# SAM_15x15_v4.net
KiCad netlist of a schematic drawn in EAGLE
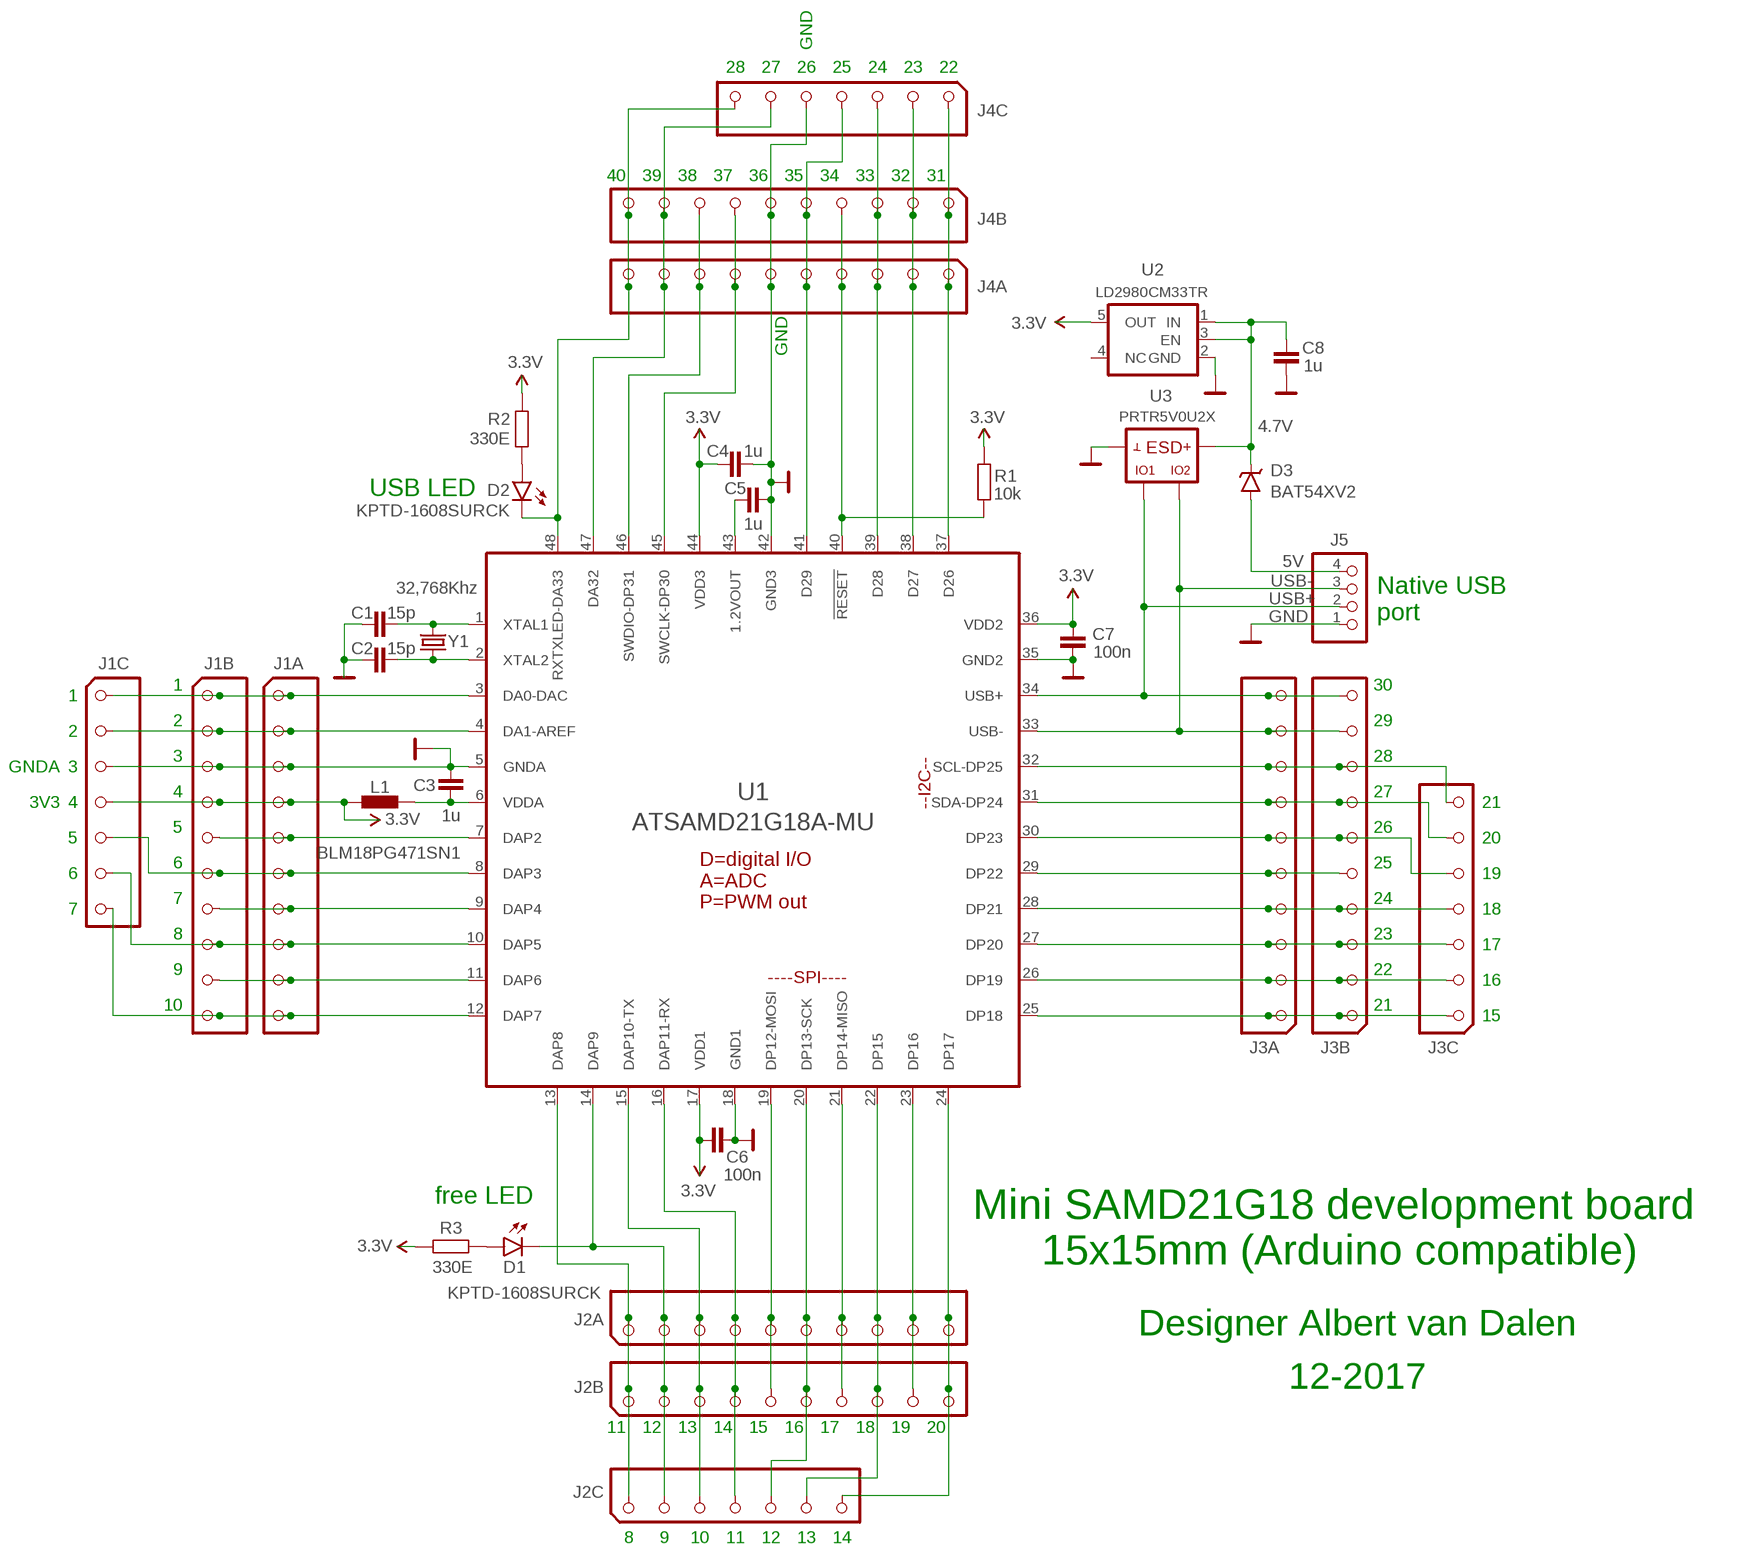
[diagram p0: schematic, sheet 1]

(export (version "E")
  (design (tool "Eeschema 10.0.6"))
  (components
    (comp (ref "C1")
      (value "15p")
      (footprint "eagle-import:0402-SMALL")
      (libsource (lib "eagle-import") (part "SMD-C-0402-SMALL"))
    )
    (comp (ref "C2")
      (value "15p")
      (footprint "eagle-import:0402-SMALL")
      (libsource (lib "eagle-import") (part "SMD-C-0402-SMALL"))
    )
    (comp (ref "C3")
      (value "1u")
      (footprint "eagle-import:0402-SMALL")
      (libsource (lib "eagle-import") (part "SMD-C-0402-SMALL"))
    )
    (comp (ref "C4")
      (value "1u")
      (footprint "eagle-import:0402-SMALL")
      (libsource (lib "eagle-import") (part "SMD-C-0402-SMALL"))
    )
    (comp (ref "C5")
      (value "1u")
      (footprint "eagle-import:0402-SMALL")
      (libsource (lib "eagle-import") (part "SMD-C-0402-SMALL"))
    )
    (comp (ref "C6")
      (value "100n")
      (footprint "eagle-import:0402-SMALL")
      (libsource (lib "eagle-import") (part "SMD-C-0402-SMALL"))
    )
    (comp (ref "C7")
      (value "100n")
      (footprint "eagle-import:0402-SMALL")
      (libsource (lib "eagle-import") (part "SMD-C-0402-SMALL"))
    )
    (comp (ref "C8")
      (value "1u")
      (footprint "eagle-import:0402-SMALL")
      (libsource (lib "eagle-import") (part "SMD-C-0402-SMALL"))
    )
    (comp (ref "D1")
      (value "KPTD-1608SURCK")
      (footprint "eagle-import:LED-0603")
      (libsource (lib "eagle-import") (part "LED"))
    )
    (comp (ref "D2")
      (value "KPTD-1608SURCK")
      (footprint "eagle-import:LED-0603")
      (libsource (lib "eagle-import") (part "LED"))
    )
    (comp (ref "D3")
      (value "BAT54XV2")
      (footprint "eagle-import:SOD523")
      (libsource (lib "eagle-import") (part "DIODE-SMDSOD523"))
    )
    (comp (ref "J1A")
      (value "JST-10SAM50")
      (footprint "eagle-import:1.27MM-10P-SAM50")
      (libsource (lib "eagle-import") (part "JST-10SAM50"))
    )
    (comp (ref "J1B")
      (value "JST-101X10")
      (footprint "eagle-import:1X10")
      (libsource (lib "eagle-import") (part "JST-101X10"))
    )
    (comp (ref "J1C")
      (value "SAM7SAM7")
      (footprint "eagle-import:SAM7")
      (libsource (lib "eagle-import") (part "SAM7SAM7"))
    )
    (comp (ref "J2A")
      (value "JST-10SAM50")
      (footprint "eagle-import:1.27MM-10P-SAM50")
      (libsource (lib "eagle-import") (part "JST-10SAM50"))
    )
    (comp (ref "J2B")
      (value "JST-101X10")
      (footprint "eagle-import:1X10")
      (libsource (lib "eagle-import") (part "JST-101X10"))
    )
    (comp (ref "J2C")
      (value "SAM7SAM7")
      (footprint "eagle-import:SAM7")
      (libsource (lib "eagle-import") (part "SAM7SAM7"))
    )
    (comp (ref "J3A")
      (value "JST-10SAM50")
      (footprint "eagle-import:1.27MM-10P-SAM50")
      (libsource (lib "eagle-import") (part "JST-10SAM50"))
    )
    (comp (ref "J3B")
      (value "JST-101X10")
      (footprint "eagle-import:1X10")
      (libsource (lib "eagle-import") (part "JST-101X10"))
    )
    (comp (ref "J3C")
      (value "SAM7SAM7")
      (footprint "eagle-import:SAM7")
      (libsource (lib "eagle-import") (part "SAM7SAM7"))
    )
    (comp (ref "J4A")
      (value "JST-10SAM50")
      (footprint "eagle-import:1.27MM-10P-SAM50")
      (libsource (lib "eagle-import") (part "JST-10SAM50"))
    )
    (comp (ref "J4B")
      (value "JST-101X10")
      (footprint "eagle-import:1X10")
      (libsource (lib "eagle-import") (part "JST-101X10"))
    )
    (comp (ref "J4C")
      (value "SAM7SAM7")
      (footprint "eagle-import:SAM7")
      (libsource (lib "eagle-import") (part "SAM7SAM7"))
    )
    (comp (ref "J5")
      (value "Header 4p")
      (footprint "eagle-import:1X04")
      (libsource (lib "eagle-import") (part "JST-41X04"))
    )
    (comp (ref "L1")
      (value "BLM18PG471SN1")
      (footprint "eagle-import:ARDUINO_C0603")
      (libsource (lib "eagle-import") (part "ARDUINO_INDUCTOR-0603"))
    )
    (comp (ref "R1")
      (value "10k")
      (footprint "eagle-import:0402-SMALL")
      (libsource (lib "eagle-import") (part "SMD-R-0402-SMALL"))
    )
    (comp (ref "R2")
      (value "330E")
      (footprint "eagle-import:0402-SMALL")
      (libsource (lib "eagle-import") (part "SMD-R-0402-SMALL"))
    )
    (comp (ref "R3")
      (value "330E")
      (footprint "eagle-import:0402-SMALL")
      (libsource (lib "eagle-import") (part "SMD-R-0402-SMALL"))
    )
    (comp (ref "U1")
      (value "ATSAMD21G18A-MU")
      (footprint "eagle-import:QFN-48")
      (libsource (lib "eagle-import") (part "ATSAMD21G-M"))
    )
    (comp (ref "U2")
      (value "LD2980CM33TR")
      (footprint "eagle-import:SOT23-5")
      (libsource (lib "eagle-import") (part "AP2112K-3.3TRG1"))
    )
    (comp (ref "U3")
      (value "PRTR5V0U2X")
      (footprint "eagle-import:SOT143B")
      (libsource (lib "eagle-import") (part "PRTR5V0U2X"))
    )
    (comp (ref "Y1")
      (value "32,768Khz")
      (footprint "eagle-import:CRYSTAL-SMD-3.2X1.5MM")
      (libsource (lib "eagle-import") (part "CRYSTAL-SMD"))
    )
  )
  (nets
    (net (code "1") (name "/3.3V") (class "Default")
      (node (ref "C4") (pin "2") (pinfunction "2_2") (pintype "passive"))
      (node (ref "C6") (pin "2") (pinfunction "2_2") (pintype "passive"))
      (node (ref "C7") (pin "2") (pinfunction "2_2") (pintype "passive"))
      (node (ref "J1A") (pin "4") (pinfunction "4_4") (pintype "passive"))
      (node (ref "J1B") (pin "4") (pinfunction "4_4") (pintype "passive"))
      (node (ref "J1C") (pin "4") (pinfunction "4_4") (pintype "passive"))
      (node (ref "L1") (pin "1") (pinfunction "1_1") (pintype "passive"))
      (node (ref "R1") (pin "2") (pinfunction "2_2") (pintype "passive"))
      (node (ref "R2") (pin "2") (pinfunction "2_2") (pintype "passive"))
      (node (ref "R3") (pin "2") (pinfunction "2_2") (pintype "passive"))
      (node (ref "U1") (pin "17") (pinfunction "VDD1_17") (pintype "bidirectional"))
      (node (ref "U1") (pin "36") (pinfunction "VDD2_36") (pintype "bidirectional"))
      (node (ref "U1") (pin "44") (pinfunction "VDD3_44") (pintype "bidirectional"))
      (node (ref "U2") (pin "5") (pinfunction "OUT_5") (pintype "passive"))
    )
    (net (code "2") (name "/4.7V") (class "Default")
      (node (ref "C8") (pin "2") (pinfunction "2_2") (pintype "passive"))
      (node (ref "D3") (pin "C") (pinfunction "C_C") (pintype "passive"))
      (node (ref "U2") (pin "1") (pinfunction "IN_1") (pintype "input"))
      (node (ref "U2") (pin "3") (pinfunction "EN_3") (pintype "input"))
      (node (ref "U3") (pin "4") (pinfunction "VCC_4") (pintype "bidirectional"))
    )
    (net (code "3") (name "/5V") (class "Default")
      (node (ref "D3") (pin "A") (pinfunction "A_A") (pintype "passive"))
      (node (ref "J5") (pin "4") (pinfunction "4_4") (pintype "passive"))
    )
    (net (code "4") (name "/USB+") (class "Default")
      (node (ref "J3A") (pin "10") (pinfunction "10_10") (pintype "passive"))
      (node (ref "J3B") (pin "10") (pinfunction "10_10") (pintype "passive"))
      (node (ref "J5") (pin "2") (pinfunction "2_2") (pintype "passive"))
      (node (ref "U1") (pin "34") (pinfunction "USB+_34") (pintype "bidirectional"))
      (node (ref "U3") (pin "3") (pinfunction "IO1_3") (pintype "bidirectional"))
    )
    (net (code "5") (name "/USB-") (class "Default")
      (node (ref "J3A") (pin "9") (pinfunction "9_9") (pintype "passive"))
      (node (ref "J3B") (pin "9") (pinfunction "9_9") (pintype "passive"))
      (node (ref "J5") (pin "3") (pinfunction "3_3") (pintype "passive"))
      (node (ref "U1") (pin "33") (pinfunction "USB-_33") (pintype "bidirectional"))
      (node (ref "U3") (pin "2") (pinfunction "IO2_2") (pintype "bidirectional"))
    )
    (net (code "6") (name "GND") (class "Default")
      (node (ref "C1") (pin "2") (pinfunction "2_2") (pintype "passive"))
      (node (ref "C2") (pin "2") (pinfunction "2_2") (pintype "passive"))
      (node (ref "C3") (pin "2") (pinfunction "2_2") (pintype "passive"))
      (node (ref "C4") (pin "1") (pinfunction "1_1") (pintype "passive"))
      (node (ref "C5") (pin "1") (pinfunction "1_1") (pintype "passive"))
      (node (ref "C6") (pin "1") (pinfunction "1_1") (pintype "passive"))
      (node (ref "C7") (pin "1") (pinfunction "1_1") (pintype "passive"))
      (node (ref "C8") (pin "1") (pinfunction "1_1") (pintype "passive"))
      (node (ref "J1A") (pin "3") (pinfunction "3_3") (pintype "passive"))
      (node (ref "J1B") (pin "3") (pinfunction "3_3") (pintype "passive"))
      (node (ref "J1C") (pin "3") (pinfunction "3_3") (pintype "passive"))
      (node (ref "J4A") (pin "6") (pinfunction "6_6") (pintype "passive"))
      (node (ref "J4B") (pin "6") (pinfunction "6_6") (pintype "passive"))
      (node (ref "J4C") (pin "5") (pinfunction "5_5") (pintype "passive"))
      (node (ref "J5") (pin "1") (pinfunction "1_1") (pintype "passive"))
      (node (ref "U1") (pin "18") (pinfunction "GND1_18") (pintype "bidirectional"))
      (node (ref "U1") (pin "35") (pinfunction "GND2_35") (pintype "bidirectional"))
      (node (ref "U1") (pin "42") (pinfunction "GND3_42") (pintype "bidirectional"))
      (node (ref "U1") (pin "5") (pinfunction "GNDA_5") (pintype "bidirectional"))
      (node (ref "U2") (pin "2") (pinfunction "GND_2") (pintype "input"))
      (node (ref "U3") (pin "1") (pinfunction "GND_1") (pintype "bidirectional"))
    )
    (net (code "7") (name "Net-(D1-PadA)") (class "Default")
      (node (ref "D1") (pin "A") (pinfunction "A_A") (pintype "passive"))
      (node (ref "R3") (pin "1") (pinfunction "1_1") (pintype "passive"))
    )
    (net (code "8") (name "Net-(D2-PadA)") (class "Default")
      (node (ref "D2") (pin "A") (pinfunction "A_A") (pintype "passive"))
      (node (ref "R2") (pin "1") (pinfunction "1_1") (pintype "passive"))
    )
    (net (code "9") (name "Net-(U1-1.2VOUT)") (class "Default")
      (node (ref "C5") (pin "2") (pinfunction "2_2") (pintype "passive"))
      (node (ref "U1") (pin "43") (pinfunction "1.2VOUT_43") (pintype "bidirectional"))
    )
    (net (code "10") (name "Net-(U1-D26)") (class "Default")
      (node (ref "J4A") (pin "1") (pinfunction "1_1") (pintype "passive"))
      (node (ref "J4B") (pin "1") (pinfunction "1_1") (pintype "passive"))
      (node (ref "J4C") (pin "1") (pinfunction "1_1") (pintype "passive"))
      (node (ref "U1") (pin "37") (pinfunction "D26_37") (pintype "bidirectional"))
    )
    (net (code "11") (name "Net-(U1-D27)") (class "Default")
      (node (ref "J4A") (pin "2") (pinfunction "2_2") (pintype "passive"))
      (node (ref "J4B") (pin "2") (pinfunction "2_2") (pintype "passive"))
      (node (ref "J4C") (pin "2") (pinfunction "2_2") (pintype "passive"))
      (node (ref "U1") (pin "38") (pinfunction "D27_38") (pintype "bidirectional"))
    )
    (net (code "12") (name "Net-(U1-D28)") (class "Default")
      (node (ref "J4A") (pin "3") (pinfunction "3_3") (pintype "passive"))
      (node (ref "J4B") (pin "3") (pinfunction "3_3") (pintype "passive"))
      (node (ref "J4C") (pin "3") (pinfunction "3_3") (pintype "passive"))
      (node (ref "U1") (pin "39") (pinfunction "D28_39") (pintype "bidirectional"))
    )
    (net (code "13") (name "Net-(U1-D29)") (class "Default")
      (node (ref "J4A") (pin "5") (pinfunction "5_5") (pintype "passive"))
      (node (ref "J4B") (pin "5") (pinfunction "5_5") (pintype "passive"))
      (node (ref "J4C") (pin "4") (pinfunction "4_4") (pintype "passive"))
      (node (ref "U1") (pin "41") (pinfunction "D29_41") (pintype "bidirectional"))
    )
    (net (code "14") (name "Net-(U1-DA0-DAC)") (class "Default")
      (node (ref "J1A") (pin "1") (pinfunction "1_1") (pintype "passive"))
      (node (ref "J1B") (pin "1") (pinfunction "1_1") (pintype "passive"))
      (node (ref "J1C") (pin "1") (pinfunction "1_1") (pintype "passive"))
      (node (ref "U1") (pin "3") (pinfunction "DA0-DAC_3") (pintype "bidirectional"))
    )
    (net (code "15") (name "Net-(U1-DA1-AREF)") (class "Default")
      (node (ref "J1A") (pin "2") (pinfunction "2_2") (pintype "passive"))
      (node (ref "J1B") (pin "2") (pinfunction "2_2") (pintype "passive"))
      (node (ref "J1C") (pin "2") (pinfunction "2_2") (pintype "passive"))
      (node (ref "U1") (pin "4") (pinfunction "DA1-AREF_4") (pintype "bidirectional"))
    )
    (net (code "16") (name "Net-(U1-DA32)") (class "Default")
      (node (ref "J4A") (pin "9") (pinfunction "9_9") (pintype "passive"))
      (node (ref "J4B") (pin "9") (pinfunction "9_9") (pintype "passive"))
      (node (ref "J4C") (pin "6") (pinfunction "6_6") (pintype "passive"))
      (node (ref "U1") (pin "47") (pinfunction "DA32_47") (pintype "bidirectional"))
    )
    (net (code "17") (name "Net-(U1-DAP2)") (class "Default")
      (node (ref "J1A") (pin "5") (pinfunction "5_5") (pintype "passive"))
      (node (ref "J1B") (pin "5") (pinfunction "5_5") (pintype "passive"))
      (node (ref "U1") (pin "7") (pinfunction "DAP2_7") (pintype "bidirectional"))
    )
    (net (code "18") (name "Net-(U1-DAP3)") (class "Default")
      (node (ref "J1A") (pin "6") (pinfunction "6_6") (pintype "passive"))
      (node (ref "J1B") (pin "6") (pinfunction "6_6") (pintype "passive"))
      (node (ref "J1C") (pin "5") (pinfunction "5_5") (pintype "passive"))
      (node (ref "U1") (pin "8") (pinfunction "DAP3_8") (pintype "bidirectional"))
    )
    (net (code "19") (name "Net-(U1-DAP4)") (class "Default")
      (node (ref "J1A") (pin "7") (pinfunction "7_7") (pintype "passive"))
      (node (ref "J1B") (pin "7") (pinfunction "7_7") (pintype "passive"))
      (node (ref "U1") (pin "9") (pinfunction "DAP4_9") (pintype "bidirectional"))
    )
    (net (code "20") (name "Net-(U1-DAP5)") (class "Default")
      (node (ref "J1A") (pin "8") (pinfunction "8_8") (pintype "passive"))
      (node (ref "J1B") (pin "8") (pinfunction "8_8") (pintype "passive"))
      (node (ref "J1C") (pin "6") (pinfunction "6_6") (pintype "passive"))
      (node (ref "U1") (pin "10") (pinfunction "DAP5_10") (pintype "bidirectional"))
    )
    (net (code "21") (name "Net-(U1-DAP6)") (class "Default")
      (node (ref "J1A") (pin "9") (pinfunction "9_9") (pintype "passive"))
      (node (ref "J1B") (pin "9") (pinfunction "9_9") (pintype "passive"))
      (node (ref "U1") (pin "11") (pinfunction "DAP6_11") (pintype "bidirectional"))
    )
    (net (code "22") (name "Net-(U1-DAP7)") (class "Default")
      (node (ref "J1A") (pin "10") (pinfunction "10_10") (pintype "passive"))
      (node (ref "J1B") (pin "10") (pinfunction "10_10") (pintype "passive"))
      (node (ref "J1C") (pin "7") (pinfunction "7_7") (pintype "passive"))
      (node (ref "U1") (pin "12") (pinfunction "DAP7_12") (pintype "bidirectional"))
    )
    (net (code "23") (name "Net-(U1-DAP8)") (class "Default")
      (node (ref "J2A") (pin "1") (pinfunction "1_1") (pintype "passive"))
      (node (ref "J2B") (pin "1") (pinfunction "1_1") (pintype "passive"))
      (node (ref "J2C") (pin "1") (pinfunction "1_1") (pintype "passive"))
      (node (ref "U1") (pin "13") (pinfunction "DAP8_13") (pintype "bidirectional"))
    )
    (net (code "24") (name "Net-(U1-DAP9)") (class "Default")
      (node (ref "D1") (pin "C") (pinfunction "C_C") (pintype "passive"))
      (node (ref "J2A") (pin "2") (pinfunction "2_2") (pintype "passive"))
      (node (ref "J2B") (pin "2") (pinfunction "2_2") (pintype "passive"))
      (node (ref "J2C") (pin "2") (pinfunction "2_2") (pintype "passive"))
      (node (ref "U1") (pin "14") (pinfunction "DAP9_14") (pintype "bidirectional"))
    )
    (net (code "25") (name "Net-(U1-DAP10-TX)") (class "Default")
      (node (ref "J2A") (pin "3") (pinfunction "3_3") (pintype "passive"))
      (node (ref "J2B") (pin "3") (pinfunction "3_3") (pintype "passive"))
      (node (ref "J2C") (pin "3") (pinfunction "3_3") (pintype "passive"))
      (node (ref "U1") (pin "15") (pinfunction "DAP10-TX_15") (pintype "bidirectional"))
    )
    (net (code "26") (name "Net-(U1-DAP11-RX)") (class "Default")
      (node (ref "J2A") (pin "4") (pinfunction "4_4") (pintype "passive"))
      (node (ref "J2B") (pin "4") (pinfunction "4_4") (pintype "passive"))
      (node (ref "J2C") (pin "4") (pinfunction "4_4") (pintype "passive"))
      (node (ref "U1") (pin "16") (pinfunction "DAP11-RX_16") (pintype "bidirectional"))
    )
    (net (code "27") (name "Net-(U1-DP12-MOSI)") (class "Default")
      (node (ref "J2A") (pin "5") (pinfunction "5_5") (pintype "passive"))
      (node (ref "J2B") (pin "5") (pinfunction "5_5") (pintype "passive"))
      (node (ref "U1") (pin "19") (pinfunction "DP12-MOSI_19") (pintype "bidirectional"))
    )
    (net (code "28") (name "Net-(U1-DP13-SCK)") (class "Default")
      (node (ref "J2A") (pin "6") (pinfunction "6_6") (pintype "passive"))
      (node (ref "J2B") (pin "6") (pinfunction "6_6") (pintype "passive"))
      (node (ref "J2C") (pin "5") (pinfunction "5_5") (pintype "passive"))
      (node (ref "U1") (pin "20") (pinfunction "DP13-SCK_20") (pintype "bidirectional"))
    )
    (net (code "29") (name "Net-(U1-DP14-MISO)") (class "Default")
      (node (ref "J2A") (pin "7") (pinfunction "7_7") (pintype "passive"))
      (node (ref "J2B") (pin "7") (pinfunction "7_7") (pintype "passive"))
      (node (ref "U1") (pin "21") (pinfunction "DP14-MISO_21") (pintype "bidirectional"))
    )
    (net (code "30") (name "Net-(U1-DP15)") (class "Default")
      (node (ref "J2A") (pin "8") (pinfunction "8_8") (pintype "passive"))
      (node (ref "J2B") (pin "8") (pinfunction "8_8") (pintype "passive"))
      (node (ref "J2C") (pin "6") (pinfunction "6_6") (pintype "passive"))
      (node (ref "U1") (pin "22") (pinfunction "DP15_22") (pintype "bidirectional"))
    )
    (net (code "31") (name "Net-(U1-DP16)") (class "Default")
      (node (ref "J2A") (pin "9") (pinfunction "9_9") (pintype "passive"))
      (node (ref "J2B") (pin "9") (pinfunction "9_9") (pintype "passive"))
      (node (ref "U1") (pin "23") (pinfunction "DP16_23") (pintype "bidirectional"))
    )
    (net (code "32") (name "Net-(U1-DP17)") (class "Default")
      (node (ref "J2A") (pin "10") (pinfunction "10_10") (pintype "passive"))
      (node (ref "J2B") (pin "10") (pinfunction "10_10") (pintype "passive"))
      (node (ref "J2C") (pin "7") (pinfunction "7_7") (pintype "passive"))
      (node (ref "U1") (pin "24") (pinfunction "DP17_24") (pintype "bidirectional"))
    )
    (net (code "33") (name "Net-(U1-DP18)") (class "Default")
      (node (ref "J3A") (pin "1") (pinfunction "1_1") (pintype "passive"))
      (node (ref "J3B") (pin "1") (pinfunction "1_1") (pintype "passive"))
      (node (ref "J3C") (pin "1") (pinfunction "1_1") (pintype "passive"))
      (node (ref "U1") (pin "25") (pinfunction "DP18_25") (pintype "bidirectional"))
    )
    (net (code "34") (name "Net-(U1-DP19)") (class "Default")
      (node (ref "J3A") (pin "2") (pinfunction "2_2") (pintype "passive"))
      (node (ref "J3B") (pin "2") (pinfunction "2_2") (pintype "passive"))
      (node (ref "J3C") (pin "2") (pinfunction "2_2") (pintype "passive"))
      (node (ref "U1") (pin "26") (pinfunction "DP19_26") (pintype "bidirectional"))
    )
    (net (code "35") (name "Net-(U1-DP20)") (class "Default")
      (node (ref "J3A") (pin "3") (pinfunction "3_3") (pintype "passive"))
      (node (ref "J3B") (pin "3") (pinfunction "3_3") (pintype "passive"))
      (node (ref "J3C") (pin "3") (pinfunction "3_3") (pintype "passive"))
      (node (ref "U1") (pin "27") (pinfunction "DP20_27") (pintype "bidirectional"))
    )
    (net (code "36") (name "Net-(U1-DP21)") (class "Default")
      (node (ref "J3A") (pin "4") (pinfunction "4_4") (pintype "passive"))
      (node (ref "J3B") (pin "4") (pinfunction "4_4") (pintype "passive"))
      (node (ref "J3C") (pin "4") (pinfunction "4_4") (pintype "passive"))
      (node (ref "U1") (pin "28") (pinfunction "DP21_28") (pintype "bidirectional"))
    )
    (net (code "37") (name "Net-(U1-DP22)") (class "Default")
      (node (ref "J3A") (pin "5") (pinfunction "5_5") (pintype "passive"))
      (node (ref "J3B") (pin "5") (pinfunction "5_5") (pintype "passive"))
      (node (ref "U1") (pin "29") (pinfunction "DP22_29") (pintype "bidirectional"))
    )
    (net (code "38") (name "Net-(U1-DP23)") (class "Default")
      (node (ref "J3A") (pin "6") (pinfunction "6_6") (pintype "passive"))
      (node (ref "J3B") (pin "6") (pinfunction "6_6") (pintype "passive"))
      (node (ref "J3C") (pin "5") (pinfunction "5_5") (pintype "passive"))
      (node (ref "U1") (pin "30") (pinfunction "DP23_30") (pintype "bidirectional"))
    )
    (net (code "39") (name "Net-(U1-RXTXLED-DA33)") (class "Default")
      (node (ref "D2") (pin "C") (pinfunction "C_C") (pintype "passive"))
      (node (ref "J4A") (pin "10") (pinfunction "10_10") (pintype "passive"))
      (node (ref "J4B") (pin "10") (pinfunction "10_10") (pintype "passive"))
      (node (ref "J4C") (pin "7") (pinfunction "7_7") (pintype "passive"))
      (node (ref "U1") (pin "48") (pinfunction "RXTXLED-DA33_48") (pintype "bidirectional"))
    )
    (net (code "40") (name "Net-(U1-SCL-DP25)") (class "Default")
      (node (ref "J3A") (pin "8") (pinfunction "8_8") (pintype "passive"))
      (node (ref "J3B") (pin "8") (pinfunction "8_8") (pintype "passive"))
      (node (ref "J3C") (pin "7") (pinfunction "7_7") (pintype "passive"))
      (node (ref "U1") (pin "32") (pinfunction "SCL-DP25_32") (pintype "bidirectional"))
    )
    (net (code "41") (name "Net-(U1-SDA-DP24)") (class "Default")
      (node (ref "J3A") (pin "7") (pinfunction "7_7") (pintype "passive"))
      (node (ref "J3B") (pin "7") (pinfunction "7_7") (pintype "passive"))
      (node (ref "J3C") (pin "6") (pinfunction "6_6") (pintype "passive"))
      (node (ref "U1") (pin "31") (pinfunction "SDA-DP24_31") (pintype "bidirectional"))
    )
    (net (code "42") (name "Net-(U1-SWCLK-DP30)") (class "Default")
      (node (ref "J4A") (pin "7") (pinfunction "7_7") (pintype "passive"))
      (node (ref "J4B") (pin "7") (pinfunction "7_7") (pintype "passive"))
      (node (ref "U1") (pin "45") (pinfunction "SWCLK-DP30_45") (pintype "bidirectional"))
    )
    (net (code "43") (name "Net-(U1-SWDIO-DP31)") (class "Default")
      (node (ref "J4A") (pin "8") (pinfunction "8_8") (pintype "passive"))
      (node (ref "J4B") (pin "8") (pinfunction "8_8") (pintype "passive"))
      (node (ref "U1") (pin "46") (pinfunction "SWDIO-DP31_46") (pintype "bidirectional"))
    )
    (net (code "44") (name "Net-(U1-VDDA)") (class "Default")
      (node (ref "C3") (pin "1") (pinfunction "1_1") (pintype "passive"))
      (node (ref "L1") (pin "2") (pinfunction "2_2") (pintype "passive"))
      (node (ref "U1") (pin "6") (pinfunction "VDDA_6") (pintype "bidirectional"))
    )
    (net (code "45") (name "Net-(U1-XTAL1)") (class "Default")
      (node (ref "C1") (pin "1") (pinfunction "1_1") (pintype "passive"))
      (node (ref "U1") (pin "1") (pinfunction "XTAL1_1") (pintype "bidirectional"))
      (node (ref "Y1") (pin "P$2") (pinfunction "2_P$2") (pintype "bidirectional"))
    )
    (net (code "46") (name "Net-(U1-XTAL2)") (class "Default")
      (node (ref "C2") (pin "1") (pinfunction "1_1") (pintype "passive"))
      (node (ref "U1") (pin "2") (pinfunction "XTAL2_2") (pintype "bidirectional"))
      (node (ref "Y1") (pin "P$1") (pinfunction "1_P$1") (pintype "bidirectional"))
    )
    (net (code "47") (name "Net-(U1-~{RESET})") (class "Default")
      (node (ref "J4A") (pin "4") (pinfunction "4_4") (pintype "passive"))
      (node (ref "J4B") (pin "4") (pinfunction "4_4") (pintype "passive"))
      (node (ref "R1") (pin "1") (pinfunction "1_1") (pintype "passive"))
      (node (ref "U1") (pin "40") (pinfunction "~{RESET}_40") (pintype "bidirectional"))
    )
    (net (code "48") (name "unconnected-(U2-NC-Pad4)") (class "Default")
      (node (ref "U2") (pin "4") (pinfunction "NC_4") (pintype "no_connect"))
    )
  )
)
